# MOTOR_CONTROL.net
KiCad netlist of a schematic drawn in EasyEDA
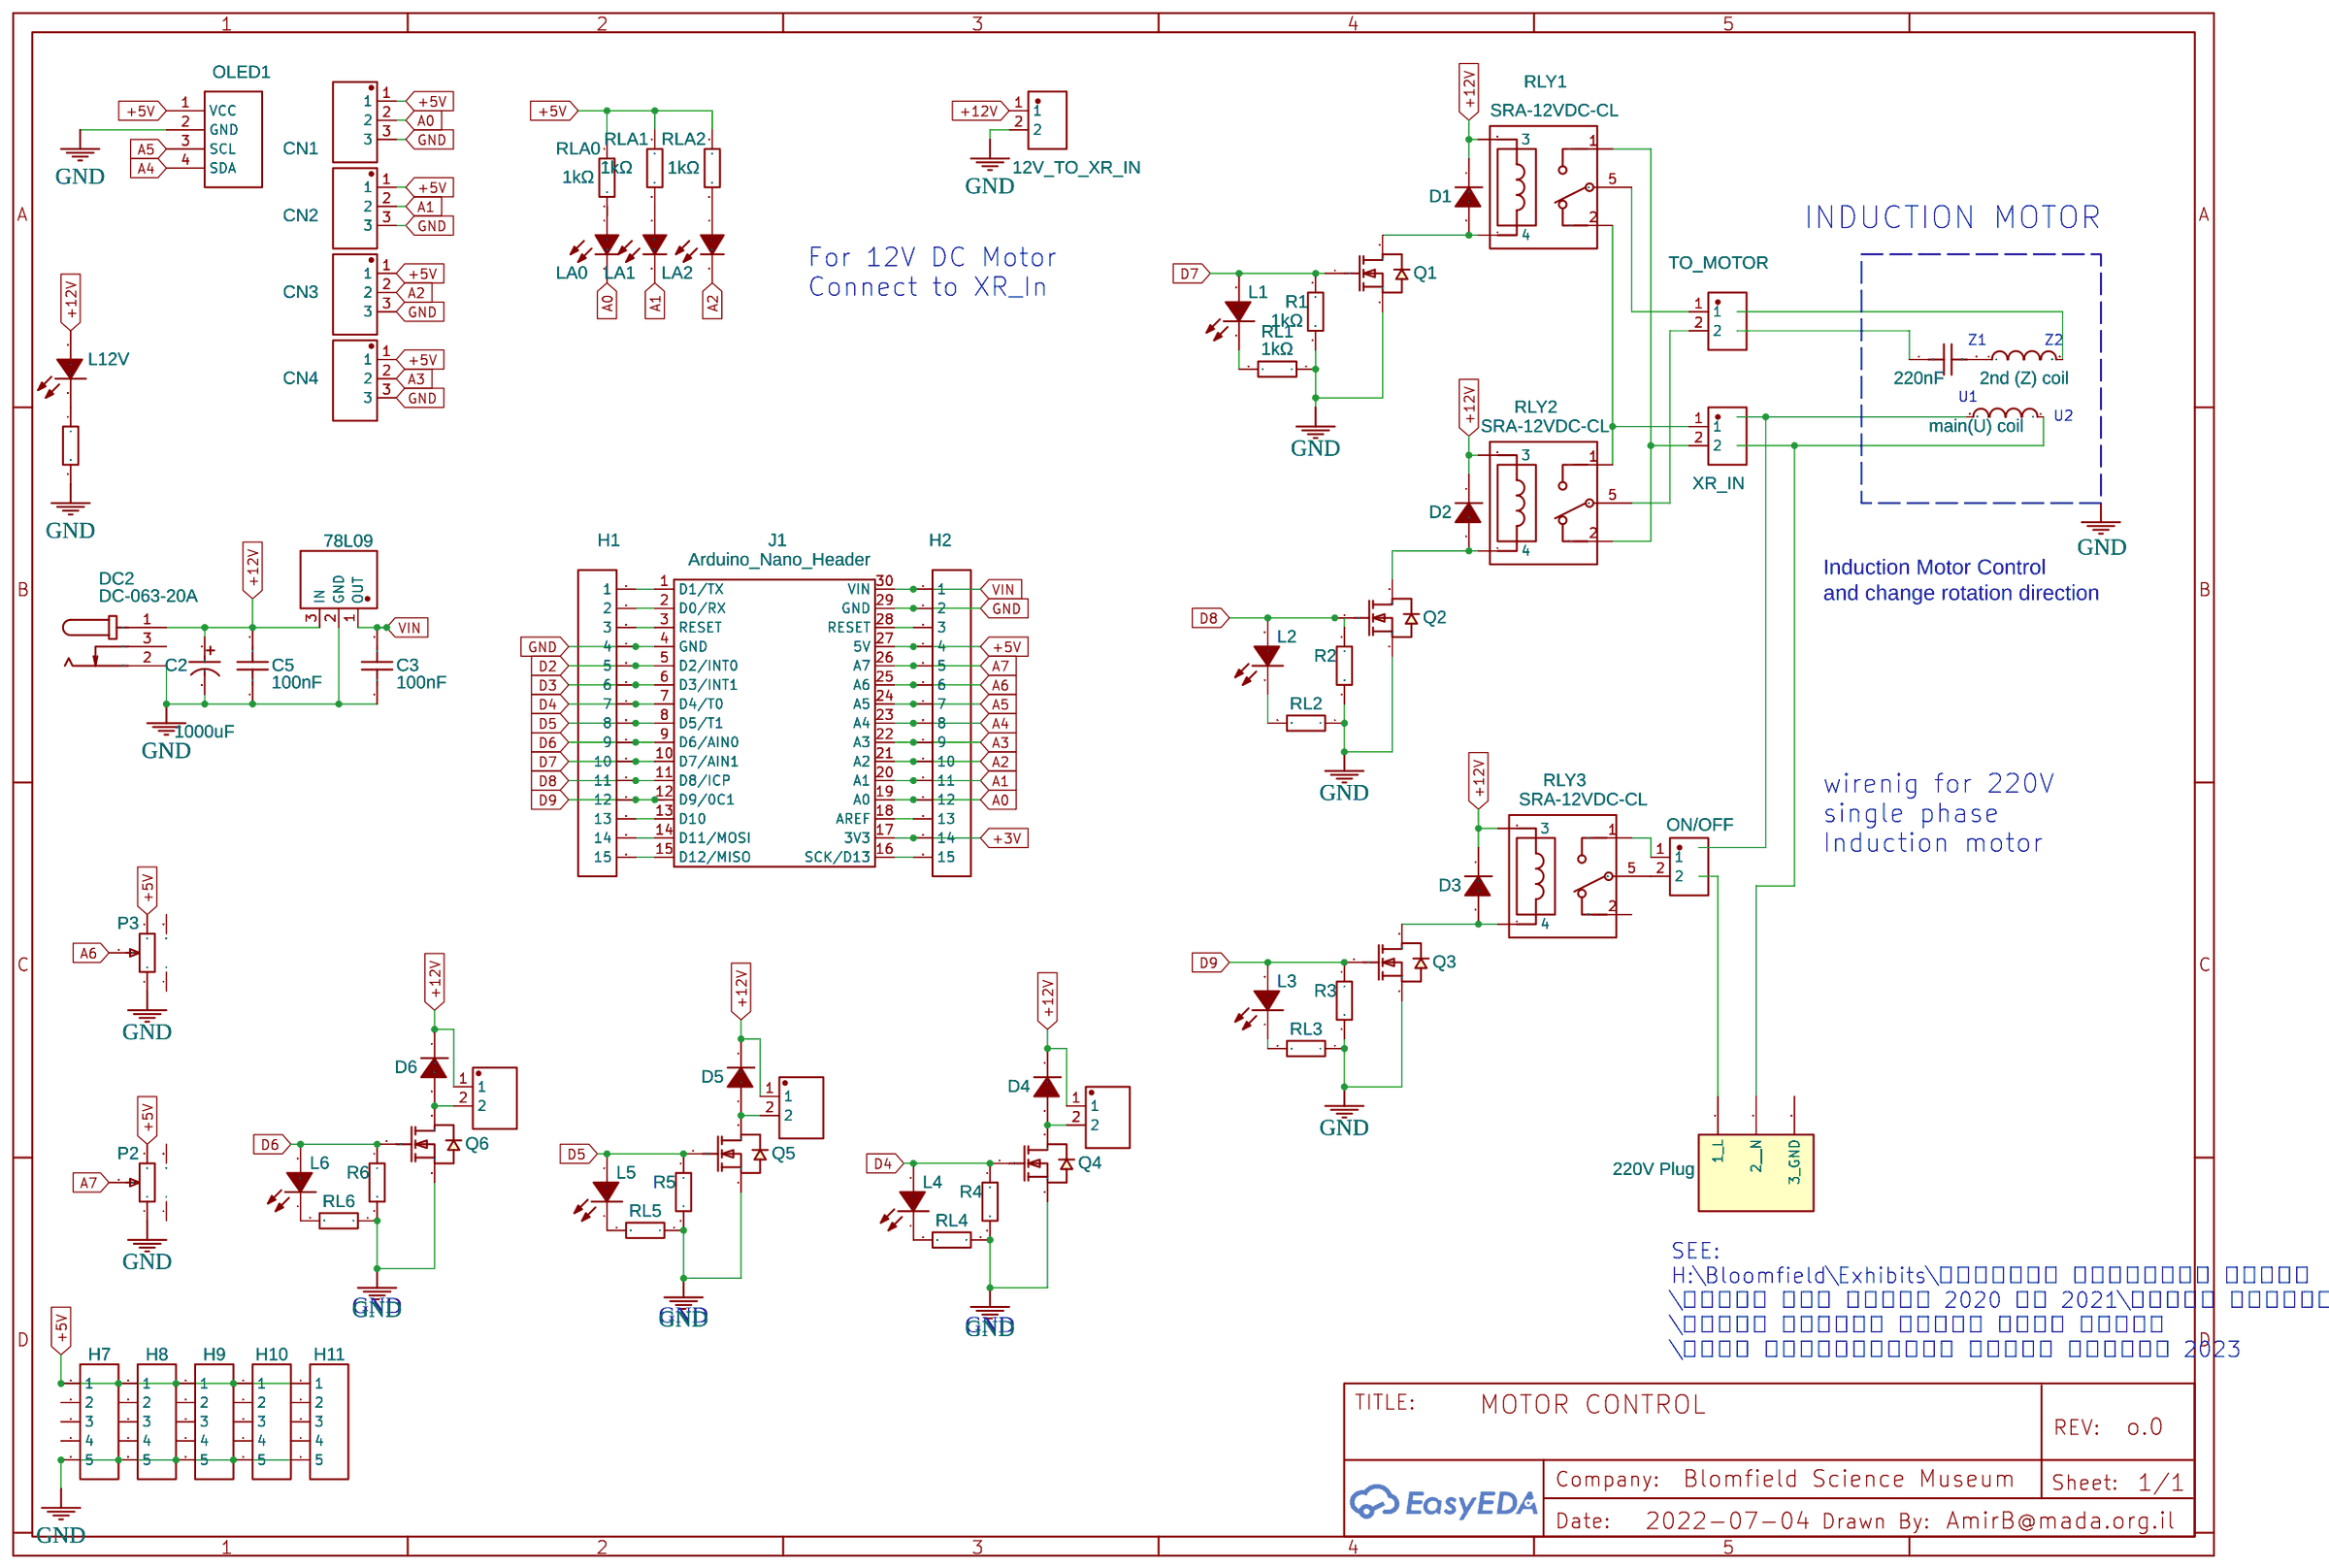
[diagram p0: schematic sheet]

(export (version "E")
  (design (tool "Eeschema 10.0.6"))
  (components
    (comp (ref "12V_TO_XR_IN")
      (value "12V_TO_R")
      (fields
        (field (name "BOM_Manufacturer Part") "KF301-5.0-2P")
        (field (name "BOM_Supplier Part") "C474881")
      )
      (libsource (lib "") (part "KF301-5.0-2P_3"))
    )
    (comp (ref "ACON1")
      (value "KF2510-2A")
      (fields (field (name "BOM_Supplier Part") "C27543"))
      (libsource (lib "") (part "KF2510-2A"))
    )
    (comp (ref "ACON2")
      (value "KF2510-2A")
      (fields (field (name "BOM_Supplier Part") "C27543"))
      (libsource (lib "") (part "KF2510-2A"))
    )
    (comp (ref "ACON3")
      (value "KF2510-2A")
      (fields (field (name "BOM_Supplier Part") "C27543"))
      (libsource (lib "") (part "KF2510-2A"))
    )
    (comp (ref "C2")
      (value "1000uF")
      (fields (field (name "BOM_Manufacturer Part") "1000uF 50V") (field (name "BOM_Supplier Part") "C18104"))
      (libsource (lib "") (part "1000uF 50V"))
    )
    (comp (ref "C3")
      (value "100nF")
      (fields
        (field (name "BOM_Manufacturer Part") "CC0603KRX7R9BB104")
        (field (name "BOM_Supplier Part") "C14663")
      )
      (libsource (lib "") (part "CC0603KRX7R9BB104"))
    )
    (comp (ref "C4") (value "220nF") (libsource (lib "") (part "C_0603_US")))
    (comp (ref "C5")
      (value "100nF")
      (fields
        (field (name "BOM_Manufacturer Part") "CC0603KRX7R9BB104")
        (field (name "BOM_Supplier Part") "C14663")
      )
      (libsource (lib "") (part "CC0603KRX7R9BB104"))
    )
    (comp (ref "CN1")
      (value "KF2510-3PFlat knitting needle")
      (fields (field (name "BOM_Supplier Part") "C45011"))
      (libsource (lib "") (part "KF2510-3PFlat knitting needle"))
    )
    (comp (ref "CN2")
      (value "KF2510-3PFlat knitting needle")
      (fields (field (name "BOM_Supplier Part") "C45011"))
      (libsource (lib "") (part "KF2510-3PFlat knitting needle"))
    )
    (comp (ref "CN3")
      (value "KF2510-3PFlat knitting needle")
      (fields (field (name "BOM_Supplier Part") "C45011"))
      (libsource (lib "") (part "KF2510-3PFlat knitting needle"))
    )
    (comp (ref "CN4")
      (value "KF2510-3PFlat knitting needle")
      (fields (field (name "BOM_Supplier Part") "C45011"))
      (libsource (lib "") (part "KF2510-3PFlat knitting needle"))
    )
    (comp (ref "CR3")
      (value "ON/OFF")
      (fields
        (field (name "BOM_Manufacturer Part") "KF301-5.0-2P")
        (field (name "BOM_Supplier Part") "C474881")
      )
      (libsource (lib "") (part "KF301-5.0-2P_1"))
    )
    (comp (ref "D1")
      (value "M7_C95872")
      (fields (field (name "Manufacturer Part") "M7") (field (name "Manufacturer") "MDD"))
      (libsource (lib "") (part "M7_C95872"))
    )
    (comp (ref "D2")
      (value "M7_C95872")
      (fields (field (name "Manufacturer Part") "M7") (field (name "Manufacturer") "MDD"))
      (libsource (lib "") (part "M7_C95872"))
    )
    (comp (ref "D3")
      (value "M7_C95872")
      (fields (field (name "Manufacturer Part") "M7") (field (name "Manufacturer") "MDD"))
      (libsource (lib "") (part "M7_C95872"))
    )
    (comp (ref "D4")
      (value "M7_C95872")
      (fields (field (name "Manufacturer Part") "M7") (field (name "Manufacturer") "MDD"))
      (libsource (lib "") (part "M7_C95872"))
    )
    (comp (ref "D5")
      (value "M7_C95872")
      (fields (field (name "Manufacturer Part") "M7") (field (name "Manufacturer") "MDD"))
      (libsource (lib "") (part "M7_C95872"))
    )
    (comp (ref "D6")
      (value "M7_C95872")
      (fields (field (name "Manufacturer Part") "M7") (field (name "Manufacturer") "MDD"))
      (libsource (lib "") (part "M7_C95872"))
    )
    (comp (ref "DC2")
      (value "DC-063-20A")
      (fields (field (name "BOM_Supplier Part") "C707268"))
      (libsource (lib "") (part "DC-063-20A"))
    )
    (comp (ref "H1")
      (value "HDR-F-2.54_1x15")
      (fields (field (name "BOM_Supplier Part") "C124408"))
      (libsource (lib "") (part "HDR-F-2.54_1x15_1"))
    )
    (comp (ref "H2")
      (value "HDR-F-2.54_1x15")
      (fields (field (name "BOM_Supplier Part") "C124408"))
      (libsource (lib "") (part "HDR-F-2.54_1x15"))
    )
    (comp (ref "H7")
      (value "HDR-F-2.54_1x5")
      (fields (field (name "BOM_Supplier Part") "C50950"))
      (libsource (lib "") (part "HDR-F-2.54_1x5"))
    )
    (comp (ref "H8")
      (value "HDR-F-2.54_1x5")
      (fields (field (name "BOM_Supplier Part") "C50950"))
      (libsource (lib "") (part "HDR-F-2.54_1x5"))
    )
    (comp (ref "H9")
      (value "HDR-F-2.54_1x5")
      (fields (field (name "BOM_Supplier Part") "C50950"))
      (libsource (lib "") (part "HDR-F-2.54_1x5"))
    )
    (comp (ref "H10")
      (value "HDR-F-2.54_1x5")
      (fields (field (name "BOM_Supplier Part") "C50950"))
      (libsource (lib "") (part "HDR-F-2.54_1x5"))
    )
    (comp (ref "H11")
      (value "HDR-F-2.54_1x5")
      (fields (field (name "BOM_Supplier Part") "C50950"))
      (libsource (lib "") (part "HDR-F-2.54_1x5"))
    )
    (comp (ref "J1") (value "Arduino_Nano_Header") (libsource (lib "") (part "Arduino_Nano_Header")))
    (comp (ref "L1")
      (value "FC-2012HRK-620D")
      (fields (field (name "BOM_Supplier Part") "C84256"))
      (libsource (lib "") (part "FC-2012HRK-620D"))
    )
    (comp (ref "L2")
      (value "FC-2012HRK-620D")
      (fields (field (name "BOM_Supplier Part") "C84256"))
      (libsource (lib "") (part "FC-2012HRK-620D"))
    )
    (comp (ref "L3")
      (value "FC-2012HRK-620D")
      (fields (field (name "BOM_Supplier Part") "C84256"))
      (libsource (lib "") (part "FC-2012HRK-620D"))
    )
    (comp (ref "L4")
      (value "FC-2012HRK-620D")
      (fields (field (name "BOM_Supplier Part") "C84256"))
      (libsource (lib "") (part "FC-2012HRK-620D"))
    )
    (comp (ref "L5")
      (value "FC-2012HRK-620D")
      (fields (field (name "BOM_Supplier Part") "C84256"))
      (libsource (lib "") (part "FC-2012HRK-620D"))
    )
    (comp (ref "L6")
      (value "FC-2012HRK-620D")
      (fields (field (name "BOM_Supplier Part") "C84256"))
      (libsource (lib "") (part "FC-2012HRK-620D"))
    )
    (comp (ref "L9") (value "main(U) coil") (libsource (lib "") (part "L0603_US_1")))
    (comp (ref "L10") (value "2nd (Z) coil") (libsource (lib "") (part "L0603_US")))
    (comp (ref "L12V")
      (value "FC-2012HRK-620D")
      (fields (field (name "BOM_Supplier Part") "C84256"))
      (libsource (lib "") (part "FC-2012HRK-620D_1"))
    )
    (comp (ref "LA0")
      (value "19-217/BHC-ZL1M2RY/3T")
      (fields (field (name "BOM_Supplier Part") "C72041"))
      (libsource (lib "") (part "19-217/BHC-ZL1M2RY/3T"))
    )
    (comp (ref "LA1")
      (value "19-217/BHC-ZL1M2RY/3T")
      (fields (field (name "BOM_Supplier Part") "C72041"))
      (libsource (lib "") (part "19-217/BHC-ZL1M2RY/3T"))
    )
    (comp (ref "LA2")
      (value "19-217/BHC-ZL1M2RY/3T")
      (fields (field (name "BOM_Supplier Part") "C72041"))
      (libsource (lib "") (part "19-217/BHC-ZL1M2RY/3T"))
    )
    (comp (ref "OLED1")
      (value "1.3 inch OLED SSH1106 I2C 128x64 copy")
      (libsource (lib "") (part "1.3 inch OLED SSH1106 I2C 128x64 copy"))
    )
    (comp (ref "P2")
      (value "长柄旋转电位器")
      (fields (field (name "BOM_Supplier Part") "C2874842"))
      (libsource (lib "") (part "长柄旋转电位器"))
    )
    (comp (ref "P3")
      (value "长柄旋转电位器")
      (fields (field (name "BOM_Supplier Part") "C2874842"))
      (libsource (lib "") (part "长柄旋转电位器"))
    )
    (comp (ref "P4")
      (value "220V Plug")
      (fields (field (name "BOM_Supplier Part") "C49661"))
      (libsource (lib "") (part "Main voltage"))
    )
    (comp (ref "Q1")
      (value "AO3400A")
      (fields (field (name "Manufacturer") "AOS"))
      (libsource (lib "") (part "AO3400A"))
    )
    (comp (ref "Q2")
      (value "AO3400A")
      (fields (field (name "Manufacturer") "AOS"))
      (libsource (lib "") (part "AO3400A"))
    )
    (comp (ref "Q3")
      (value "AO3400A")
      (fields (field (name "Manufacturer") "AOS"))
      (libsource (lib "") (part "AO3400A"))
    )
    (comp (ref "Q4")
      (value "AO3400A")
      (fields (field (name "Manufacturer") "AOS"))
      (libsource (lib "") (part "AO3400A"))
    )
    (comp (ref "Q5")
      (value "AO3400A")
      (fields (field (name "Manufacturer") "AOS"))
      (libsource (lib "") (part "AO3400A"))
    )
    (comp (ref "Q6")
      (value "AO3400A")
      (fields (field (name "Manufacturer") "AOS"))
      (libsource (lib "") (part "AO3400A"))
    )
    (comp (ref "R1")
      (value "1kΩ")
      (fields
        (field (name "BOM_Manufacturer Part") "0603WAF1001T5E")
        (field (name "BOM_Supplier Part") "C21190")
      )
      (libsource (lib "") (part "0603WAF1001T5E_3"))
    )
    (comp (ref "R2")
      (value "1kΩ")
      (fields
        (field (name "BOM_Manufacturer Part") "0603WAF1001T5E")
        (field (name "BOM_Supplier Part") "C21190")
      )
      (libsource (lib "") (part "0603WAF1001T5E"))
    )
    (comp (ref "R3")
      (value "1kΩ")
      (fields
        (field (name "BOM_Manufacturer Part") "0603WAF1001T5E")
        (field (name "BOM_Supplier Part") "C21190")
      )
      (libsource (lib "") (part "0603WAF1001T5E"))
    )
    (comp (ref "R4")
      (value "1kΩ")
      (fields
        (field (name "BOM_Manufacturer Part") "0603WAF1001T5E")
        (field (name "BOM_Supplier Part") "C21190")
      )
      (libsource (lib "") (part "0603WAF1001T5E"))
    )
    (comp (ref "R5")
      (value "1kΩ")
      (fields
        (field (name "BOM_Manufacturer Part") "0603WAF1001T5E")
        (field (name "BOM_Supplier Part") "C21190")
      )
      (libsource (lib "") (part "0603WAF1001T5E"))
    )
    (comp (ref "R6")
      (value "1kΩ")
      (fields
        (field (name "BOM_Manufacturer Part") "0603WAF1001T5E")
        (field (name "BOM_Supplier Part") "C21190")
      )
      (libsource (lib "") (part "0603WAF1001T5E"))
    )
    (comp (ref "RL1")
      (value "1kΩ")
      (fields
        (field (name "BOM_Manufacturer Part") "0603WAF1001T5E")
        (field (name "BOM_Supplier Part") "C21190")
      )
      (libsource (lib "") (part "0603WAF1001T5E_1"))
    )
    (comp (ref "RL2")
      (value "1kΩ")
      (fields
        (field (name "BOM_Manufacturer Part") "0603WAF1001T5E")
        (field (name "BOM_Supplier Part") "C21190")
      )
      (libsource (lib "") (part "0603WAF1001T5E_1"))
    )
    (comp (ref "RL3")
      (value "1kΩ")
      (fields
        (field (name "BOM_Manufacturer Part") "0603WAF1001T5E")
        (field (name "BOM_Supplier Part") "C21190")
      )
      (libsource (lib "") (part "0603WAF1001T5E_1"))
    )
    (comp (ref "RL4")
      (value "1kΩ")
      (fields
        (field (name "BOM_Manufacturer Part") "0603WAF1001T5E")
        (field (name "BOM_Supplier Part") "C21190")
      )
      (libsource (lib "") (part "0603WAF1001T5E_1"))
    )
    (comp (ref "RL5")
      (value "1kΩ")
      (fields
        (field (name "BOM_Manufacturer Part") "0603WAF1001T5E")
        (field (name "BOM_Supplier Part") "C21190")
      )
      (libsource (lib "") (part "0603WAF1001T5E_1"))
    )
    (comp (ref "RL6")
      (value "1kΩ")
      (fields
        (field (name "BOM_Manufacturer Part") "0603WAF1001T5E")
        (field (name "BOM_Supplier Part") "C21190")
      )
      (libsource (lib "") (part "0603WAF1001T5E_1"))
    )
    (comp (ref "RL12V")
      (value "R10K")
      (fields
        (field (name "BOM_Manufacturer Part") "0603WAF1002T5E")
        (field (name "BOM_Supplier Part") "C25804")
      )
      (libsource (lib "") (part "0603WAF1001T5E_4"))
    )
    (comp (ref "RLA0")
      (value "1kΩ")
      (fields
        (field (name "BOM_Manufacturer Part") "0603WAF1001T5E")
        (field (name "BOM_Supplier Part") "C21190")
      )
      (libsource (lib "") (part "0603WAF1001T5E_2"))
    )
    (comp (ref "RLA1")
      (value "1kΩ")
      (fields
        (field (name "BOM_Manufacturer Part") "0603WAF1001T5E")
        (field (name "BOM_Supplier Part") "C21190")
      )
      (libsource (lib "") (part "0603WAF1001T5E_2"))
    )
    (comp (ref "RLA2")
      (value "1kΩ")
      (fields
        (field (name "BOM_Manufacturer Part") "0603WAF1001T5E")
        (field (name "BOM_Supplier Part") "C21190")
      )
      (libsource (lib "") (part "0603WAF1001T5E_2"))
    )
    (comp (ref "RLY1")
      (value "SRA-12VDC-CL")
      (fields (field (name "Manufacturer") "松乐"))
      (libsource (lib "") (part "SRA-12VDC-CL"))
    )
    (comp (ref "RLY2")
      (value "SRA-12VDC-CL")
      (fields (field (name "Manufacturer") "松乐"))
      (libsource (lib "") (part "SRA-12VDC-CL"))
    )
    (comp (ref "RLY3")
      (value "SRA-12VDC-CL")
      (fields (field (name "Manufacturer") "松乐"))
      (libsource (lib "") (part "SRA-12VDC-CL"))
    )
    (comp (ref "TO_MOTOR")
      (value "TO_MOTOR")
      (fields
        (field (name "BOM_Manufacturer Part") "KF301-5.0-2P")
        (field (name "BOM_Supplier Part") "C474881")
      )
      (libsource (lib "") (part "KF301-5.0-2P"))
    )
    (comp (ref "U5")
      (value "78L09")
      (fields (field (name "Manufacturer Part") "78L09U 78L09") (field (name "Manufacturer") "CBI(创基)"))
      (libsource (lib "") (part "78L09U 78L09"))
    )
    (comp (ref "XR_IN")
      (value "XR_IN")
      (fields
        (field (name "BOM_Manufacturer Part") "KF301-5.0-2P")
        (field (name "BOM_Supplier Part") "C474881")
      )
      (libsource (lib "") (part "KF301-5.0-2P_2"))
    )
  )
  (nets
    (net (code "1") (name "+3V") (class "Default")
      (node (ref "H2") (pin "14") (pinfunction "14_14") (pintype "unspecified"))
      (node (ref "J1") (pin "17") (pinfunction "3V3_17") (pintype "unspecified"))
    )
    (net (code "2") (name "+5V") (class "Default")
      (node (ref "CN1") (pin "1") (pinfunction "1_1") (pintype "unspecified"))
      (node (ref "CN2") (pin "1") (pinfunction "1_1") (pintype "unspecified"))
      (node (ref "CN3") (pin "1") (pinfunction "1_1") (pintype "unspecified"))
      (node (ref "CN4") (pin "1") (pinfunction "1_1") (pintype "unspecified"))
      (node (ref "H10") (pin "1") (pinfunction "1_1") (pintype "unspecified"))
      (node (ref "H11") (pin "1") (pinfunction "1_1") (pintype "unspecified"))
      (node (ref "H2") (pin "4") (pinfunction "4_4") (pintype "unspecified"))
      (node (ref "H7") (pin "1") (pinfunction "1_1") (pintype "unspecified"))
      (node (ref "H8") (pin "1") (pinfunction "1_1") (pintype "unspecified"))
      (node (ref "H9") (pin "1") (pinfunction "1_1") (pintype "unspecified"))
      (node (ref "J1") (pin "27") (pinfunction "5V_27") (pintype "unspecified"))
      (node (ref "OLED1") (pin "1") (pinfunction "VCC_1") (pintype "passive"))
      (node (ref "P2") (pin "3") (pinfunction "3_3") (pintype "input"))
      (node (ref "P3") (pin "3") (pinfunction "3_3") (pintype "input"))
      (node (ref "RLA0") (pin "1") (pinfunction "1_1") (pintype "input"))
      (node (ref "RLA1") (pin "1") (pinfunction "1_1") (pintype "input"))
      (node (ref "RLA2") (pin "1") (pinfunction "1_1") (pintype "input"))
    )
    (net (code "3") (name "+12V") (class "Default")
      (node (ref "12V_TO_XR_IN") (pin "1") (pinfunction "1_1") (pintype "unspecified"))
      (node (ref "ACON1") (pin "1") (pinfunction "1_1") (pintype "unspecified"))
      (node (ref "ACON2") (pin "1") (pinfunction "1_1") (pintype "unspecified"))
      (node (ref "ACON3") (pin "1") (pinfunction "1_1") (pintype "unspecified"))
      (node (ref "C2") (pin "1") (pinfunction "1_1") (pintype "input"))
      (node (ref "C5") (pin "2") (pinfunction "2_2") (pintype "unspecified"))
      (node (ref "D1") (pin "1") (pinfunction "K_1") (pintype "unspecified"))
      (node (ref "D2") (pin "1") (pinfunction "K_1") (pintype "unspecified"))
      (node (ref "D3") (pin "1") (pinfunction "K_1") (pintype "unspecified"))
      (node (ref "D4") (pin "1") (pinfunction "K_1") (pintype "unspecified"))
      (node (ref "D5") (pin "1") (pinfunction "K_1") (pintype "unspecified"))
      (node (ref "D6") (pin "1") (pinfunction "K_1") (pintype "unspecified"))
      (node (ref "DC2") (pin "1") (pinfunction "1_1") (pintype "unspecified"))
      (node (ref "L12V") (pin "2") (pinfunction "+_2") (pintype "unspecified"))
      (node (ref "RLY1") (pin "3") (pinfunction "3_3") (pintype "unspecified"))
      (node (ref "RLY2") (pin "3") (pinfunction "3_3") (pintype "unspecified"))
      (node (ref "RLY3") (pin "3") (pinfunction "3_3") (pintype "unspecified"))
      (node (ref "U5") (pin "3") (pinfunction "IN_3") (pintype "unspecified"))
    )
    (net (code "4") (name "A0") (class "Default")
      (node (ref "CN1") (pin "2") (pinfunction "2_2") (pintype "unspecified"))
      (node (ref "H2") (pin "12") (pinfunction "12_12") (pintype "unspecified"))
      (node (ref "J1") (pin "19") (pinfunction "A0_19") (pintype "unspecified"))
      (node (ref "LA0") (pin "2") (pinfunction "C_2") (pintype "input"))
    )
    (net (code "5") (name "A1") (class "Default")
      (node (ref "CN2") (pin "2") (pinfunction "2_2") (pintype "unspecified"))
      (node (ref "H2") (pin "11") (pinfunction "11_11") (pintype "unspecified"))
      (node (ref "J1") (pin "20") (pinfunction "A1_20") (pintype "unspecified"))
      (node (ref "LA1") (pin "2") (pinfunction "C_2") (pintype "input"))
    )
    (net (code "6") (name "A2") (class "Default")
      (node (ref "CN3") (pin "2") (pinfunction "2_2") (pintype "unspecified"))
      (node (ref "H2") (pin "10") (pinfunction "10_10") (pintype "unspecified"))
      (node (ref "J1") (pin "21") (pinfunction "A2_21") (pintype "unspecified"))
      (node (ref "LA2") (pin "2") (pinfunction "C_2") (pintype "input"))
    )
    (net (code "7") (name "A3") (class "Default")
      (node (ref "CN4") (pin "2") (pinfunction "2_2") (pintype "unspecified"))
      (node (ref "H2") (pin "9") (pinfunction "9_9") (pintype "unspecified"))
      (node (ref "J1") (pin "22") (pinfunction "A3_22") (pintype "unspecified"))
    )
    (net (code "8") (name "A4") (class "Default")
      (node (ref "H2") (pin "8") (pinfunction "8_8") (pintype "unspecified"))
      (node (ref "J1") (pin "23") (pinfunction "A4_23") (pintype "unspecified"))
      (node (ref "OLED1") (pin "4") (pinfunction "SDA_4") (pintype "bidirectional"))
    )
    (net (code "9") (name "A5") (class "Default")
      (node (ref "H2") (pin "7") (pinfunction "7_7") (pintype "unspecified"))
      (node (ref "J1") (pin "24") (pinfunction "A5_24") (pintype "unspecified"))
      (node (ref "OLED1") (pin "3") (pinfunction "SCL_3") (pintype "bidirectional"))
    )
    (net (code "10") (name "A6") (class "Default")
      (node (ref "H2") (pin "6") (pinfunction "6_6") (pintype "unspecified"))
      (node (ref "J1") (pin "25") (pinfunction "A6_25") (pintype "unspecified"))
      (node (ref "P3") (pin "2") (pinfunction "2_2") (pintype "input"))
    )
    (net (code "11") (name "A7") (class "Default")
      (node (ref "H2") (pin "5") (pinfunction "5_5") (pintype "unspecified"))
      (node (ref "J1") (pin "26") (pinfunction "A7_26") (pintype "unspecified"))
      (node (ref "P2") (pin "2") (pinfunction "2_2") (pintype "input"))
    )
    (net (code "12") (name "D2") (class "Default")
      (node (ref "H1") (pin "5") (pinfunction "5_5") (pintype "unspecified"))
      (node (ref "J1") (pin "5") (pinfunction "D2/INT0_5") (pintype "unspecified"))
    )
    (net (code "13") (name "D3") (class "Default")
      (node (ref "H1") (pin "6") (pinfunction "6_6") (pintype "unspecified"))
      (node (ref "J1") (pin "6") (pinfunction "D3/INT1_6") (pintype "unspecified"))
    )
    (net (code "14") (name "D4") (class "Default")
      (node (ref "H1") (pin "7") (pinfunction "7_7") (pintype "unspecified"))
      (node (ref "J1") (pin "7") (pinfunction "D4/T0_7") (pintype "unspecified"))
      (node (ref "L4") (pin "2") (pinfunction "+_2") (pintype "unspecified"))
      (node (ref "Q4") (pin "1") (pinfunction "G_1") (pintype "unspecified"))
      (node (ref "R4") (pin "1") (pinfunction "1_1") (pintype "input"))
    )
    (net (code "15") (name "D5") (class "Default")
      (node (ref "H1") (pin "8") (pinfunction "8_8") (pintype "unspecified"))
      (node (ref "J1") (pin "8") (pinfunction "D5/T1_8") (pintype "unspecified"))
      (node (ref "L5") (pin "2") (pinfunction "+_2") (pintype "unspecified"))
      (node (ref "Q5") (pin "1") (pinfunction "G_1") (pintype "unspecified"))
      (node (ref "R5") (pin "1") (pinfunction "1_1") (pintype "input"))
    )
    (net (code "16") (name "D6") (class "Default")
      (node (ref "H1") (pin "9") (pinfunction "9_9") (pintype "unspecified"))
      (node (ref "J1") (pin "9") (pinfunction "D6/AIN0_9") (pintype "unspecified"))
      (node (ref "L6") (pin "2") (pinfunction "+_2") (pintype "unspecified"))
      (node (ref "Q6") (pin "1") (pinfunction "G_1") (pintype "unspecified"))
      (node (ref "R6") (pin "1") (pinfunction "1_1") (pintype "input"))
    )
    (net (code "17") (name "D7") (class "Default")
      (node (ref "H1") (pin "10") (pinfunction "10_10") (pintype "unspecified"))
      (node (ref "J1") (pin "10") (pinfunction "D7/AIN1_10") (pintype "unspecified"))
      (node (ref "L1") (pin "2") (pinfunction "+_2") (pintype "unspecified"))
      (node (ref "Q1") (pin "1") (pinfunction "G_1") (pintype "unspecified"))
      (node (ref "R1") (pin "2") (pinfunction "2_2") (pintype "input"))
    )
    (net (code "18") (name "D8") (class "Default")
      (node (ref "H1") (pin "11") (pinfunction "11_11") (pintype "unspecified"))
      (node (ref "J1") (pin "11") (pinfunction "D8/ICP_11") (pintype "unspecified"))
      (node (ref "L2") (pin "2") (pinfunction "+_2") (pintype "unspecified"))
      (node (ref "Q2") (pin "1") (pinfunction "G_1") (pintype "unspecified"))
      (node (ref "R2") (pin "1") (pinfunction "1_1") (pintype "input"))
    )
    (net (code "19") (name "D9") (class "Default")
      (node (ref "H1") (pin "12") (pinfunction "12_12") (pintype "unspecified"))
      (node (ref "J1") (pin "12") (pinfunction "D9/0C1_12") (pintype "unspecified"))
      (node (ref "L3") (pin "2") (pinfunction "+_2") (pintype "unspecified"))
      (node (ref "Q3") (pin "1") (pinfunction "G_1") (pintype "unspecified"))
      (node (ref "R3") (pin "1") (pinfunction "1_1") (pintype "input"))
    )
    (net (code "20") (name "GND") (class "Default")
      (node (ref "12V_TO_XR_IN") (pin "2") (pinfunction "2_2") (pintype "unspecified"))
      (node (ref "C2") (pin "2") (pinfunction "2_2") (pintype "input"))
      (node (ref "C3") (pin "1") (pinfunction "1_1") (pintype "unspecified"))
      (node (ref "C5") (pin "1") (pinfunction "1_1") (pintype "unspecified"))
      (node (ref "CN1") (pin "3") (pinfunction "3_3") (pintype "unspecified"))
      (node (ref "CN2") (pin "3") (pinfunction "3_3") (pintype "unspecified"))
      (node (ref "CN3") (pin "3") (pinfunction "3_3") (pintype "unspecified"))
      (node (ref "CN4") (pin "3") (pinfunction "3_3") (pintype "unspecified"))
      (node (ref "DC2") (pin "2") (pinfunction "2_2") (pintype "unspecified"))
      (node (ref "H1") (pin "4") (pinfunction "4_4") (pintype "unspecified"))
      (node (ref "H10") (pin "5") (pinfunction "5_5") (pintype "unspecified"))
      (node (ref "H11") (pin "5") (pinfunction "5_5") (pintype "unspecified"))
      (node (ref "H2") (pin "2") (pinfunction "2_2") (pintype "unspecified"))
      (node (ref "H7") (pin "5") (pinfunction "5_5") (pintype "unspecified"))
      (node (ref "H8") (pin "5") (pinfunction "5_5") (pintype "unspecified"))
      (node (ref "H9") (pin "5") (pinfunction "5_5") (pintype "unspecified"))
      (node (ref "J1") (pin "29") (pinfunction "GND_29") (pintype "unspecified"))
      (node (ref "J1") (pin "4") (pinfunction "GND_4") (pintype "unspecified"))
      (node (ref "OLED1") (pin "2") (pinfunction "GND_2") (pintype "passive"))
      (node (ref "P2") (pin "1") (pinfunction "1_1") (pintype "input"))
      (node (ref "P3") (pin "1") (pinfunction "1_1") (pintype "input"))
      (node (ref "Q1") (pin "2") (pinfunction "S_2") (pintype "unspecified"))
      (node (ref "Q2") (pin "2") (pinfunction "S_2") (pintype "unspecified"))
      (node (ref "Q3") (pin "2") (pinfunction "S_2") (pintype "unspecified"))
      (node (ref "Q4") (pin "2") (pinfunction "S_2") (pintype "unspecified"))
      (node (ref "Q5") (pin "2") (pinfunction "S_2") (pintype "unspecified"))
      (node (ref "Q6") (pin "2") (pinfunction "S_2") (pintype "unspecified"))
      (node (ref "R1") (pin "1") (pinfunction "1_1") (pintype "input"))
      (node (ref "R2") (pin "2") (pinfunction "2_2") (pintype "input"))
      (node (ref "R3") (pin "2") (pinfunction "2_2") (pintype "input"))
      (node (ref "R4") (pin "2") (pinfunction "2_2") (pintype "input"))
      (node (ref "R5") (pin "2") (pinfunction "2_2") (pintype "input"))
      (node (ref "R6") (pin "2") (pinfunction "2_2") (pintype "input"))
      (node (ref "RL1") (pin "1") (pinfunction "1_1") (pintype "input"))
      (node (ref "RL12V") (pin "2") (pinfunction "2_2") (pintype "input"))
      (node (ref "RL2") (pin "1") (pinfunction "1_1") (pintype "input"))
      (node (ref "RL3") (pin "1") (pinfunction "1_1") (pintype "input"))
      (node (ref "RL4") (pin "1") (pinfunction "1_1") (pintype "input"))
      (node (ref "RL5") (pin "1") (pinfunction "1_1") (pintype "input"))
      (node (ref "RL6") (pin "1") (pinfunction "1_1") (pintype "input"))
      (node (ref "U5") (pin "2") (pinfunction "GND_2") (pintype "unspecified"))
    )
    (net (code "21") (name "Net-(C4-Pad2)") (class "Default")
      (node (ref "C4") (pin "2") (pinfunction "2_2") (pintype "unspecified"))
      (node (ref "L10") (pin "1") (pinfunction "1_1") (pintype "unspecified"))
    )
    (net (code "22") (name "Net-(CR3-Pad1)") (class "Default")
      (node (ref "CR3") (pin "1") (pinfunction "1_1") (pintype "unspecified"))
      (node (ref "RLY3") (pin "1") (pinfunction "1_1") (pintype "unspecified"))
    )
    (net (code "23") (name "Net-(CR3-Pad2)") (class "Default")
      (node (ref "CR3") (pin "2") (pinfunction "2_2") (pintype "unspecified"))
      (node (ref "RLY3") (pin "5") (pinfunction "5_5") (pintype "unspecified"))
    )
    (net (code "24") (name "Net-(D1-A)") (class "Default")
      (node (ref "D1") (pin "2") (pinfunction "A_2") (pintype "unspecified"))
      (node (ref "Q1") (pin "3") (pinfunction "D_3") (pintype "unspecified"))
      (node (ref "RLY1") (pin "4") (pinfunction "4_4") (pintype "unspecified"))
    )
    (net (code "25") (name "Net-(D2-A)") (class "Default")
      (node (ref "D2") (pin "2") (pinfunction "A_2") (pintype "unspecified"))
      (node (ref "Q2") (pin "3") (pinfunction "D_3") (pintype "unspecified"))
      (node (ref "RLY2") (pin "4") (pinfunction "4_4") (pintype "unspecified"))
    )
    (net (code "26") (name "Net-(D3-A)") (class "Default")
      (node (ref "D3") (pin "2") (pinfunction "A_2") (pintype "unspecified"))
      (node (ref "Q3") (pin "3") (pinfunction "D_3") (pintype "unspecified"))
      (node (ref "RLY3") (pin "4") (pinfunction "4_4") (pintype "unspecified"))
    )
    (net (code "27") (name "Net-(D4-A)") (class "Default")
      (node (ref "ACON1") (pin "2") (pinfunction "2_2") (pintype "unspecified"))
      (node (ref "D4") (pin "2") (pinfunction "A_2") (pintype "unspecified"))
      (node (ref "Q4") (pin "3") (pinfunction "D_3") (pintype "unspecified"))
    )
    (net (code "28") (name "Net-(D5-A)") (class "Default")
      (node (ref "ACON2") (pin "2") (pinfunction "2_2") (pintype "unspecified"))
      (node (ref "D5") (pin "2") (pinfunction "A_2") (pintype "unspecified"))
      (node (ref "Q5") (pin "3") (pinfunction "D_3") (pintype "unspecified"))
    )
    (net (code "29") (name "Net-(D6-A)") (class "Default")
      (node (ref "ACON3") (pin "2") (pinfunction "2_2") (pintype "unspecified"))
      (node (ref "D6") (pin "2") (pinfunction "A_2") (pintype "unspecified"))
      (node (ref "Q6") (pin "3") (pinfunction "D_3") (pintype "unspecified"))
    )
    (net (code "30") (name "Net-(H1-Pad3)") (class "Default")
      (node (ref "H1") (pin "3") (pinfunction "3_3") (pintype "unspecified"))
      (node (ref "J1") (pin "3") (pinfunction "RESET_3") (pintype "unspecified"))
    )
    (net (code "31") (name "Net-(H2-Pad3)") (class "Default")
      (node (ref "H2") (pin "3") (pinfunction "3_3") (pintype "unspecified"))
      (node (ref "J1") (pin "28") (pinfunction "RESET_28") (pintype "unspecified"))
    )
    (net (code "32") (name "Net-(J1-AREF)") (class "Default")
      (node (ref "H2") (pin "13") (pinfunction "13_13") (pintype "unspecified"))
      (node (ref "J1") (pin "18") (pinfunction "AREF_18") (pintype "unspecified"))
    )
    (net (code "33") (name "Net-(J1-D0{slash}RX)") (class "Default")
      (node (ref "H1") (pin "2") (pinfunction "2_2") (pintype "unspecified"))
      (node (ref "J1") (pin "2") (pinfunction "D0/RX_2") (pintype "unspecified"))
    )
    (net (code "34") (name "Net-(J1-D1{slash}TX)") (class "Default")
      (node (ref "H1") (pin "1") (pinfunction "1_1") (pintype "unspecified"))
      (node (ref "J1") (pin "1") (pinfunction "D1/TX_1") (pintype "unspecified"))
    )
    (net (code "35") (name "Net-(J1-D10)") (class "Default")
      (node (ref "H1") (pin "13") (pinfunction "13_13") (pintype "unspecified"))
      (node (ref "J1") (pin "13") (pinfunction "D10_13") (pintype "unspecified"))
    )
    (net (code "36") (name "Net-(J1-D11{slash}MOSI)") (class "Default")
      (node (ref "H1") (pin "14") (pinfunction "14_14") (pintype "unspecified"))
      (node (ref "J1") (pin "14") (pinfunction "D11/MOSI_14") (pintype "unspecified"))
    )
    (net (code "37") (name "Net-(J1-D12{slash}MISO)") (class "Default")
      (node (ref "H1") (pin "15") (pinfunction "15_15") (pintype "unspecified"))
      (node (ref "J1") (pin "15") (pinfunction "D12/MISO_15") (pintype "unspecified"))
    )
    (net (code "38") (name "Net-(J1-SCK{slash}D13)") (class "Default")
      (node (ref "H2") (pin "15") (pinfunction "15_15") (pintype "unspecified"))
      (node (ref "J1") (pin "16") (pinfunction "SCK/D13_16") (pintype "unspecified"))
    )
    (net (code "39") (name "Net-(L1--)") (class "Default")
      (node (ref "L1") (pin "1") (pinfunction "-_1") (pintype "unspecified"))
      (node (ref "RL1") (pin "2") (pinfunction "2_2") (pintype "input"))
    )
    (net (code "40") (name "Net-(L2--)") (class "Default")
      (node (ref "L2") (pin "1") (pinfunction "-_1") (pintype "unspecified"))
      (node (ref "RL2") (pin "2") (pinfunction "2_2") (pintype "input"))
    )
    (net (code "41") (name "Net-(L3--)") (class "Default")
      (node (ref "L3") (pin "1") (pinfunction "-_1") (pintype "unspecified"))
      (node (ref "RL3") (pin "2") (pinfunction "2_2") (pintype "input"))
    )
    (net (code "42") (name "Net-(L4--)") (class "Default")
      (node (ref "L4") (pin "1") (pinfunction "-_1") (pintype "unspecified"))
      (node (ref "RL4") (pin "2") (pinfunction "2_2") (pintype "input"))
    )
    (net (code "43") (name "Net-(L5--)") (class "Default")
      (node (ref "L5") (pin "1") (pinfunction "-_1") (pintype "unspecified"))
      (node (ref "RL5") (pin "2") (pinfunction "2_2") (pintype "input"))
    )
    (net (code "44") (name "Net-(L6--)") (class "Default")
      (node (ref "L6") (pin "1") (pinfunction "-_1") (pintype "unspecified"))
      (node (ref "RL6") (pin "2") (pinfunction "2_2") (pintype "input"))
    )
    (net (code "45") (name "Net-(L12V--)") (class "Default")
      (node (ref "L12V") (pin "1") (pinfunction "-_1") (pintype "unspecified"))
      (node (ref "RL12V") (pin "1") (pinfunction "1_1") (pintype "input"))
    )
    (net (code "46") (name "Net-(LA0-A)") (class "Default")
      (node (ref "LA0") (pin "1") (pinfunction "A_1") (pintype "input"))
      (node (ref "RLA0") (pin "2") (pinfunction "2_2") (pintype "input"))
    )
    (net (code "47") (name "Net-(LA1-A)") (class "Default")
      (node (ref "LA1") (pin "1") (pinfunction "A_1") (pintype "input"))
      (node (ref "RLA1") (pin "2") (pinfunction "2_2") (pintype "input"))
    )
    (net (code "48") (name "Net-(LA2-A)") (class "Default")
      (node (ref "LA2") (pin "1") (pinfunction "A_1") (pintype "input"))
      (node (ref "RLA2") (pin "2") (pinfunction "2_2") (pintype "input"))
    )
    (net (code "49") (name "Net-(P4-2__N)") (class "Default")
      (node (ref "L9") (pin "1") (pinfunction "1_1") (pintype "unspecified"))
      (node (ref "P4") (pin "2") (pinfunction "2__N_2") (pintype "input"))
    )
    (net (code "50") (name "Net-(RLY1-Pad1)") (class "Default")
      (node (ref "RLY1") (pin "1") (pinfunction "1_1") (pintype "unspecified"))
      (node (ref "RLY2") (pin "2") (pinfunction "2_2") (pintype "unspecified"))
      (node (ref "XR_IN") (pin "2") (pinfunction "2_2") (pintype "unspecified"))
    )
    (net (code "51") (name "Net-(RLY1-Pad2)") (class "Default")
      (node (ref "RLY1") (pin "2") (pinfunction "2_2") (pintype "unspecified"))
      (node (ref "RLY2") (pin "1") (pinfunction "1_1") (pintype "unspecified"))
      (node (ref "XR_IN") (pin "1") (pinfunction "1_1") (pintype "unspecified"))
    )
    (net (code "52") (name "Net-(RLY1-Pad5)") (class "Default")
      (node (ref "RLY1") (pin "5") (pinfunction "5_5") (pintype "unspecified"))
      (node (ref "TO_MOTOR") (pin "1") (pinfunction "1_1") (pintype "unspecified"))
    )
    (net (code "53") (name "Net-(RLY2-Pad5)") (class "Default")
      (node (ref "RLY2") (pin "5") (pinfunction "5_5") (pintype "unspecified"))
      (node (ref "TO_MOTOR") (pin "2") (pinfunction "2_2") (pintype "unspecified"))
    )
    (net (code "54") (name "VIN") (class "Default")
      (node (ref "C3") (pin "2") (pinfunction "2_2") (pintype "unspecified"))
      (node (ref "H2") (pin "1") (pinfunction "1_1") (pintype "unspecified"))
      (node (ref "J1") (pin "30") (pinfunction "VIN_30") (pintype "unspecified"))
      (node (ref "U5") (pin "1") (pinfunction "OUT_1") (pintype "unspecified"))
    )
    (net (code "55") (name "unconnected-(C4-Pad1)") (class "Default")
      (node (ref "C4") (pin "1") (pinfunction "1_1") (pintype "unspecified"))
    )
    (net (code "56") (name "unconnected-(DC2-Pad3)") (class "Default")
      (node (ref "DC2") (pin "3") (pinfunction "3_3") (pintype "unspecified"))
    )
    (net (code "57") (name "unconnected-(H7-Pad2)") (class "Default")
      (node (ref "H7") (pin "2") (pinfunction "2_2") (pintype "unspecified"))
    )
    (net (code "58") (name "unconnected-(H7-Pad3)") (class "Default")
      (node (ref "H7") (pin "3") (pinfunction "3_3") (pintype "unspecified"))
    )
    (net (code "59") (name "unconnected-(H7-Pad4)") (class "Default")
      (node (ref "H7") (pin "4") (pinfunction "4_4") (pintype "unspecified"))
    )
    (net (code "60") (name "unconnected-(H8-Pad2)") (class "Default")
      (node (ref "H8") (pin "2") (pinfunction "2_2") (pintype "unspecified"))
    )
    (net (code "61") (name "unconnected-(H8-Pad3)") (class "Default")
      (node (ref "H8") (pin "3") (pinfunction "3_3") (pintype "unspecified"))
    )
    (net (code "62") (name "unconnected-(H8-Pad4)") (class "Default")
      (node (ref "H8") (pin "4") (pinfunction "4_4") (pintype "unspecified"))
    )
    (net (code "63") (name "unconnected-(H9-Pad2)") (class "Default")
      (node (ref "H9") (pin "2") (pinfunction "2_2") (pintype "unspecified"))
    )
    (net (code "64") (name "unconnected-(H9-Pad3)") (class "Default")
      (node (ref "H9") (pin "3") (pinfunction "3_3") (pintype "unspecified"))
    )
    (net (code "65") (name "unconnected-(H9-Pad4)") (class "Default")
      (node (ref "H9") (pin "4") (pinfunction "4_4") (pintype "unspecified"))
    )
    (net (code "66") (name "unconnected-(H10-Pad2)") (class "Default")
      (node (ref "H10") (pin "2") (pinfunction "2_2") (pintype "unspecified"))
    )
    (net (code "67") (name "unconnected-(H10-Pad3)") (class "Default")
      (node (ref "H10") (pin "3") (pinfunction "3_3") (pintype "unspecified"))
    )
    (net (code "68") (name "unconnected-(H10-Pad4)") (class "Default")
      (node (ref "H10") (pin "4") (pinfunction "4_4") (pintype "unspecified"))
    )
    (net (code "69") (name "unconnected-(H11-Pad2)") (class "Default")
      (node (ref "H11") (pin "2") (pinfunction "2_2") (pintype "unspecified"))
    )
    (net (code "70") (name "unconnected-(H11-Pad3)") (class "Default")
      (node (ref "H11") (pin "3") (pinfunction "3_3") (pintype "unspecified"))
    )
    (net (code "71") (name "unconnected-(H11-Pad4)") (class "Default")
      (node (ref "H11") (pin "4") (pinfunction "4_4") (pintype "unspecified"))
    )
    (net (code "72") (name "unconnected-(L9-Pad2)") (class "Default")
      (node (ref "L9") (pin "2") (pinfunction "2_2") (pintype "unspecified"))
    )
    (net (code "73") (name "unconnected-(L10-Pad2)") (class "Default")
      (node (ref "L10") (pin "2") (pinfunction "2_2") (pintype "unspecified"))
    )
    (net (code "74") (name "unconnected-(P2-Pad4)") (class "Default")
      (node (ref "P2") (pin "4") (pinfunction "4_4") (pintype "input"))
    )
    (net (code "75") (name "unconnected-(P2-Pad5)") (class "Default")
      (node (ref "P2") (pin "5") (pinfunction "5_5") (pintype "input"))
    )
    (net (code "76") (name "unconnected-(P3-Pad4)") (class "Default")
      (node (ref "P3") (pin "4") (pinfunction "4_4") (pintype "input"))
    )
    (net (code "77") (name "unconnected-(P3-Pad5)") (class "Default")
      (node (ref "P3") (pin "5") (pinfunction "5_5") (pintype "input"))
    )
    (net (code "78") (name "unconnected-(P4-1_L-Pad1)") (class "Default")
      (node (ref "P4") (pin "1") (pinfunction "1_L_1") (pintype "input"))
    )
    (net (code "79") (name "unconnected-(P4-3_GND-Pad2)") (class "Default")
      (node (ref "P4") (pin "2") (pinfunction "3_GND_2") (pintype "input"))
    )
    (net (code "80") (name "unconnected-(RLY3-Pad2)") (class "Default")
      (node (ref "RLY3") (pin "2") (pinfunction "2_2") (pintype "unspecified"))
    )
  )
)
